# Periph_SCH.net
KiCad netlist of a schematic drawn in Altium Designer
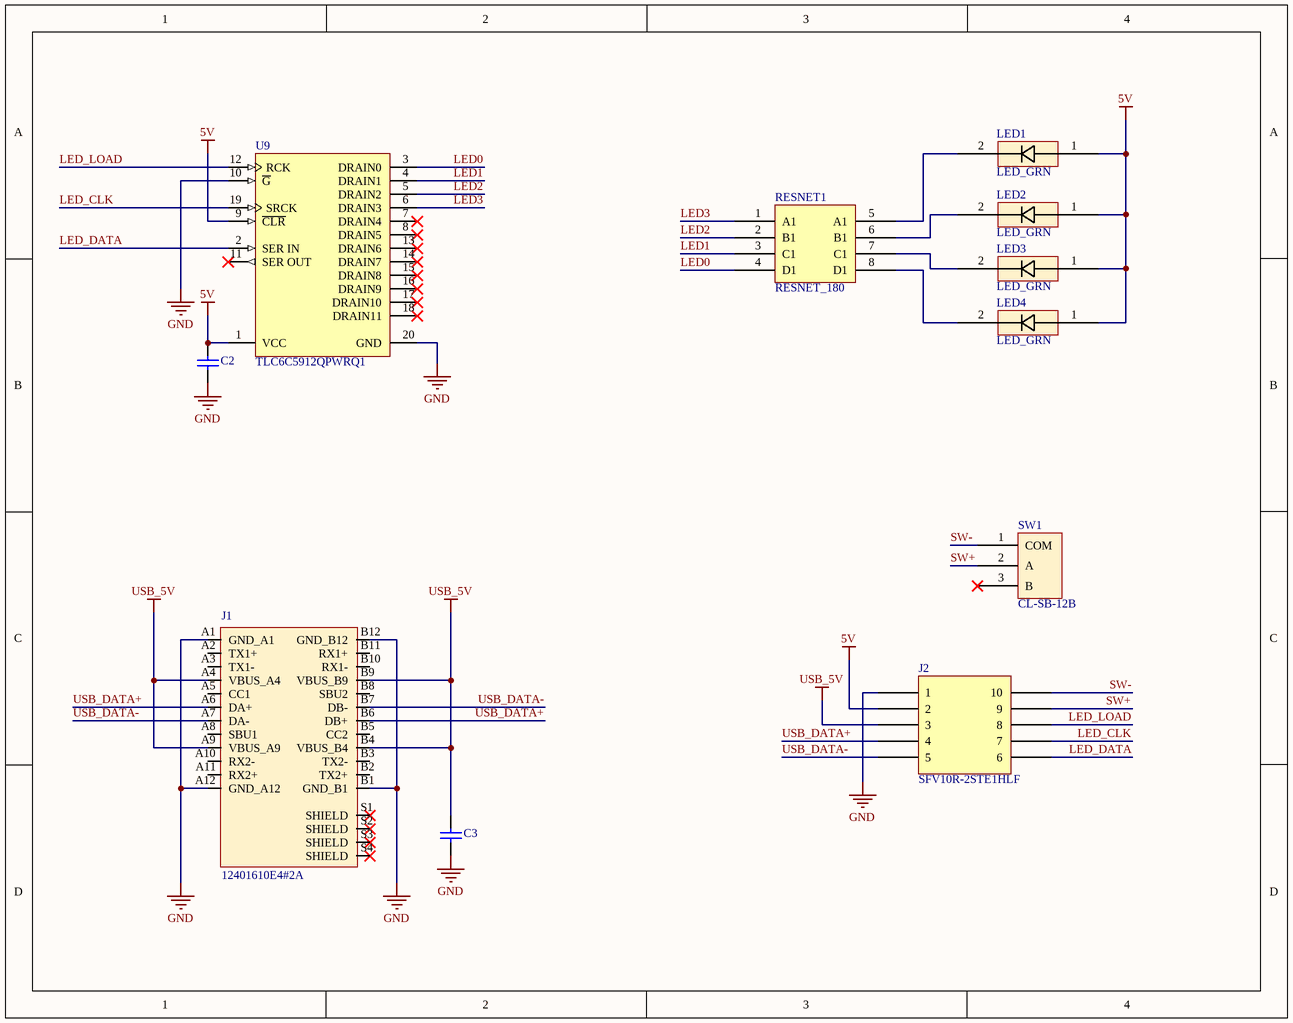
[diagram p0: Periph_SCH.SchDoc]

(export (version "E")
  (design (tool "Eeschema 10.0.6"))
  (components
    (comp (ref "C2")
      (value "08055C104KAJ2A")
      (footprint "CAPC2013X140X50NL20T25")
      (fields (field (name "MANUFACTURER") "AVX Interconnect / Elco"))
      (libsource (lib "Altium Content Vault") (part "CAP"))
    )
    (comp (ref "C3")
      (value "08055C104KAJ2A")
      (footprint "CAPC2013X140X50NL20T25")
      (fields (field (name "MANUFACTURER") "AVX Interconnect / Elco"))
      (libsource (lib "Altium Content Vault") (part "CAP"))
    )
    (comp (ref "J1")
      (value "12401610E4#2A")
      (footprint "AMPHENOL_12401610E4_2A_12401610E4")
      (description "Conn USB Type C Surface Mount Receptacle")
      (fields (field (name "MF") "Amphenol ICC") (field (name "DIGI-KEY_PART_NUMBER") "12401610E4#2ACT-ND"))
      (libsource (lib "Copter") (part "12401610E4#2A"))
    )
    (comp (ref "J2")
      (value "SFV10R-2STE1HLF")
      (footprint "SVF10R-2STE1HLF")
      (libsource (lib "Copter") (part "SFV10R-2STE1HLF"))
    )
    (comp (ref "LED1")
      (value "LED_GRN")
      (footprint "DIOC3212X08N")
      (libsource (lib "Copter") (part "LED_GRN"))
    )
    (comp (ref "LED2")
      (value "LED_GRN")
      (footprint "DIOC3212X08N")
      (libsource (lib "Copter") (part "LED_GRN"))
    )
    (comp (ref "LED3")
      (value "LED_GRN")
      (footprint "DIOC3212X08N")
      (libsource (lib "Copter") (part "LED_GRN"))
    )
    (comp (ref "LED4")
      (value "LED_GRN")
      (footprint "DIOC3212X08N")
      (libsource (lib "Copter") (part "LED_GRN"))
    )
    (comp (ref "RESNET1")
      (value "RESNET_180")
      (footprint "CAC-80P320X165-8N")
      (description "RES ARRAY 4 RES 180 OHM 2012")
      (libsource (lib "Copter") (part "RESNET_180"))
    )
    (comp (ref "SW1")
      (value "CL-SB-12B")
      (footprint "CL-SB-12B")
      (libsource (lib "Copter") (part "CL-SB-12B"))
    )
    (comp (ref "U9")
      (value "TLC6C5912QPWRQ1")
      (footprint "PW0020A_N")
      (description "Automotive Power Logic 12-Bit Shift Register LED Driver, PW0020A, LARGE T&R")
      (fields (field (name "PART NUMBER") "TLC6C5912-Q1"))
      (libsource (lib "Altium Content Vault") (part "TI-TLC6C5912-Q1-20_A"))
    )
  )
  (nets
    (net (code "1") (name "/LED0") (class "Default")
      (node (ref "RESNET1") (pin "4") (pinfunction "D1_4") (pintype "passive"))
      (node (ref "U9") (pin "3") (pinfunction "DRAIN0_3") (pintype "open_collector"))
    )
    (net (code "2") (name "/LED1") (class "Default")
      (node (ref "RESNET1") (pin "3") (pinfunction "C1_3") (pintype "passive"))
      (node (ref "U9") (pin "4") (pinfunction "DRAIN1_4") (pintype "open_collector"))
    )
    (net (code "3") (name "/LED2") (class "Default")
      (node (ref "RESNET1") (pin "2") (pinfunction "B1_2") (pintype "passive"))
      (node (ref "U9") (pin "5") (pinfunction "DRAIN2_5") (pintype "open_collector"))
    )
    (net (code "4") (name "/LED3") (class "Default")
      (node (ref "RESNET1") (pin "1") (pinfunction "A1_1") (pintype "passive"))
      (node (ref "U9") (pin "6") (pinfunction "DRAIN3_6") (pintype "open_collector"))
    )
    (net (code "5") (name "/LED_CLK") (class "Default")
      (node (ref "J2") (pin "7") (pinfunction "7_7") (pintype "passive"))
      (node (ref "U9") (pin "19") (pinfunction "SRCK_19") (pintype "input"))
    )
    (net (code "6") (name "/LED_DATA") (class "Default")
      (node (ref "J2") (pin "6") (pinfunction "6_6") (pintype "passive"))
      (node (ref "U9") (pin "2") (pinfunction "SER_IN_2") (pintype "input"))
    )
    (net (code "7") (name "/LED_LOAD") (class "Default")
      (node (ref "J2") (pin "8") (pinfunction "8_8") (pintype "passive"))
      (node (ref "U9") (pin "12") (pinfunction "RCK_12") (pintype "input"))
    )
    (net (code "8") (name "/SW+") (class "Default")
      (node (ref "J2") (pin "9") (pinfunction "9_9") (pintype "passive"))
      (node (ref "SW1") (pin "2") (pinfunction "A_2") (pintype "passive"))
    )
    (net (code "9") (name "/SW-") (class "Default")
      (node (ref "J2") (pin "10") (pinfunction "10_10") (pintype "passive"))
      (node (ref "SW1") (pin "1") (pinfunction "COM_1") (pintype "passive"))
    )
    (net (code "10") (name "/USB_DATA+") (class "Default")
      (node (ref "J1") (pin "A6") (pinfunction "DA+_A6") (pintype "passive"))
      (node (ref "J1") (pin "B6") (pinfunction "DB+_B6") (pintype "passive"))
      (node (ref "J2") (pin "4") (pinfunction "4_4") (pintype "passive"))
    )
    (net (code "11") (name "/USB_DATA-") (class "Default")
      (node (ref "J1") (pin "A7") (pinfunction "DA-_A7") (pintype "passive"))
      (node (ref "J1") (pin "B7") (pinfunction "DB-_B7") (pintype "passive"))
      (node (ref "J2") (pin "5") (pinfunction "5_5") (pintype "passive"))
    )
    (net (code "12") (name "5V") (class "Default")
      (node (ref "C2") (pin "2") (pinfunction "2_2") (pintype "passive"))
      (node (ref "J2") (pin "2") (pinfunction "2_2") (pintype "passive"))
      (node (ref "LED1") (pin "1") (pinfunction "Anode_1") (pintype "passive"))
      (node (ref "LED2") (pin "1") (pinfunction "Anode_1") (pintype "passive"))
      (node (ref "LED3") (pin "1") (pinfunction "Anode_1") (pintype "passive"))
      (node (ref "LED4") (pin "1") (pinfunction "Anode_1") (pintype "passive"))
      (node (ref "U9") (pin "1") (pinfunction "VCC_1") (pintype "power_in"))
      (node (ref "U9") (pin "9") (pinfunction "~{CLR}_9") (pintype "input"))
    )
    (net (code "13") (name "GND") (class "Default")
      (node (ref "C2") (pin "1") (pinfunction "1_1") (pintype "passive"))
      (node (ref "C3") (pin "1") (pinfunction "1_1") (pintype "passive"))
      (node (ref "J1") (pin "A1") (pinfunction "GND_A1_A1") (pintype "passive"))
      (node (ref "J1") (pin "A12") (pinfunction "GND_A12_A12") (pintype "passive"))
      (node (ref "J1") (pin "B1") (pinfunction "GND_B1_B1") (pintype "passive"))
      (node (ref "J1") (pin "B12") (pinfunction "GND_B12_B12") (pintype "passive"))
      (node (ref "J2") (pin "1") (pinfunction "1_1") (pintype "passive"))
      (node (ref "U9") (pin "10") (pinfunction "~{G}_10") (pintype "input"))
      (node (ref "U9") (pin "20") (pinfunction "GND_20") (pintype "power_in"))
    )
    (net (code "14") (name "Net-(LED1-Cathode)") (class "Default")
      (node (ref "LED1") (pin "2") (pinfunction "Cathode_2") (pintype "passive"))
      (node (ref "RESNET1") (pin "5") (pinfunction "A1_5") (pintype "passive"))
    )
    (net (code "15") (name "Net-(LED2-Cathode)") (class "Default")
      (node (ref "LED2") (pin "2") (pinfunction "Cathode_2") (pintype "passive"))
      (node (ref "RESNET1") (pin "6") (pinfunction "B1_6") (pintype "passive"))
    )
    (net (code "16") (name "Net-(LED3-Cathode)") (class "Default")
      (node (ref "LED3") (pin "2") (pinfunction "Cathode_2") (pintype "passive"))
      (node (ref "RESNET1") (pin "7") (pinfunction "C1_7") (pintype "passive"))
    )
    (net (code "17") (name "Net-(LED4-Cathode)") (class "Default")
      (node (ref "LED4") (pin "2") (pinfunction "Cathode_2") (pintype "passive"))
      (node (ref "RESNET1") (pin "8") (pinfunction "D1_8") (pintype "passive"))
    )
    (net (code "18") (name "USB_5V") (class "Default")
      (node (ref "C3") (pin "2") (pinfunction "2_2") (pintype "passive"))
      (node (ref "J1") (pin "A4") (pinfunction "VBUS_A4_A4") (pintype "passive"))
      (node (ref "J1") (pin "A9") (pinfunction "VBUS_A9_A9") (pintype "passive"))
      (node (ref "J1") (pin "B4") (pinfunction "VBUS_B4_B4") (pintype "passive"))
      (node (ref "J1") (pin "B9") (pinfunction "VBUS_B9_B9") (pintype "passive"))
      (node (ref "J2") (pin "3") (pinfunction "3_3") (pintype "passive"))
    )
    (net (code "19") (name "unconnected-(J1-CC1-PadA5)") (class "Default")
      (node (ref "J1") (pin "A5") (pinfunction "CC1_A5") (pintype "passive"))
    )
    (net (code "20") (name "unconnected-(J1-CC2-PadB5)") (class "Default")
      (node (ref "J1") (pin "B5") (pinfunction "CC2_B5") (pintype "passive"))
    )
    (net (code "21") (name "unconnected-(J1-RX1+-PadB11)") (class "Default")
      (node (ref "J1") (pin "B11") (pinfunction "RX1+_B11") (pintype "passive"))
    )
    (net (code "22") (name "unconnected-(J1-RX1--PadB10)") (class "Default")
      (node (ref "J1") (pin "B10") (pinfunction "RX1-_B10") (pintype "passive"))
    )
    (net (code "23") (name "unconnected-(J1-RX2+-PadA11)") (class "Default")
      (node (ref "J1") (pin "A11") (pinfunction "RX2+_A11") (pintype "passive"))
    )
    (net (code "24") (name "unconnected-(J1-RX2--PadA10)") (class "Default")
      (node (ref "J1") (pin "A10") (pinfunction "RX2-_A10") (pintype "passive"))
    )
    (net (code "25") (name "unconnected-(J1-SBU1-PadA8)") (class "Default")
      (node (ref "J1") (pin "A8") (pinfunction "SBU1_A8") (pintype "passive"))
    )
    (net (code "26") (name "unconnected-(J1-SBU2-PadB8)") (class "Default")
      (node (ref "J1") (pin "B8") (pinfunction "SBU2_B8") (pintype "passive"))
    )
    (net (code "27") (name "unconnected-(J1-SHIELD-PadS1)") (class "Default")
      (node (ref "J1") (pin "S1") (pinfunction "SHIELD_S1") (pintype "passive+no_connect"))
    )
    (net (code "28") (name "unconnected-(J1-SHIELD-PadS2)") (class "Default")
      (node (ref "J1") (pin "S2") (pinfunction "SHIELD_S2") (pintype "passive+no_connect"))
    )
    (net (code "29") (name "unconnected-(J1-SHIELD-PadS3)") (class "Default")
      (node (ref "J1") (pin "S3") (pinfunction "SHIELD_S3") (pintype "passive+no_connect"))
    )
    (net (code "30") (name "unconnected-(J1-SHIELD-PadS4)") (class "Default")
      (node (ref "J1") (pin "S4") (pinfunction "SHIELD_S4") (pintype "passive+no_connect"))
    )
    (net (code "31") (name "unconnected-(J1-TX1+-PadA2)") (class "Default")
      (node (ref "J1") (pin "A2") (pinfunction "TX1+_A2") (pintype "passive"))
    )
    (net (code "32") (name "unconnected-(J1-TX1--PadA3)") (class "Default")
      (node (ref "J1") (pin "A3") (pinfunction "TX1-_A3") (pintype "passive"))
    )
    (net (code "33") (name "unconnected-(J1-TX2+-PadB2)") (class "Default")
      (node (ref "J1") (pin "B2") (pinfunction "TX2+_B2") (pintype "passive"))
    )
    (net (code "34") (name "unconnected-(J1-TX2--PadB3)") (class "Default")
      (node (ref "J1") (pin "B3") (pinfunction "TX2-_B3") (pintype "passive"))
    )
    (net (code "35") (name "unconnected-(SW1-B-Pad3)") (class "Default")
      (node (ref "SW1") (pin "3") (pinfunction "B_3") (pintype "passive+no_connect"))
    )
    (net (code "36") (name "unconnected-(U9-DRAIN4-Pad7)") (class "Default")
      (node (ref "U9") (pin "7") (pinfunction "DRAIN4_7") (pintype "open_collector+no_connect"))
    )
    (net (code "37") (name "unconnected-(U9-DRAIN5-Pad8)") (class "Default")
      (node (ref "U9") (pin "8") (pinfunction "DRAIN5_8") (pintype "open_collector+no_connect"))
    )
    (net (code "38") (name "unconnected-(U9-DRAIN6-Pad13)") (class "Default")
      (node (ref "U9") (pin "13") (pinfunction "DRAIN6_13") (pintype "open_collector+no_connect"))
    )
    (net (code "39") (name "unconnected-(U9-DRAIN7-Pad14)") (class "Default")
      (node (ref "U9") (pin "14") (pinfunction "DRAIN7_14") (pintype "open_collector+no_connect"))
    )
    (net (code "40") (name "unconnected-(U9-DRAIN8-Pad15)") (class "Default")
      (node (ref "U9") (pin "15") (pinfunction "DRAIN8_15") (pintype "open_collector+no_connect"))
    )
    (net (code "41") (name "unconnected-(U9-DRAIN9-Pad16)") (class "Default")
      (node (ref "U9") (pin "16") (pinfunction "DRAIN9_16") (pintype "open_collector+no_connect"))
    )
    (net (code "42") (name "unconnected-(U9-DRAIN10-Pad17)") (class "Default")
      (node (ref "U9") (pin "17") (pinfunction "DRAIN10_17") (pintype "open_collector+no_connect"))
    )
    (net (code "43") (name "unconnected-(U9-DRAIN11-Pad18)") (class "Default")
      (node (ref "U9") (pin "18") (pinfunction "DRAIN11_18") (pintype "open_collector+no_connect"))
    )
    (net (code "44") (name "unconnected-(U9-SER_OUT-Pad11)") (class "Default")
      (node (ref "U9") (pin "11") (pinfunction "SER_OUT_11") (pintype "output+no_connect"))
    )
  )
)
